# pc_healthypi_move_nRF5340_v5.net
KiCad netlist of a schematic drawn in EAGLE
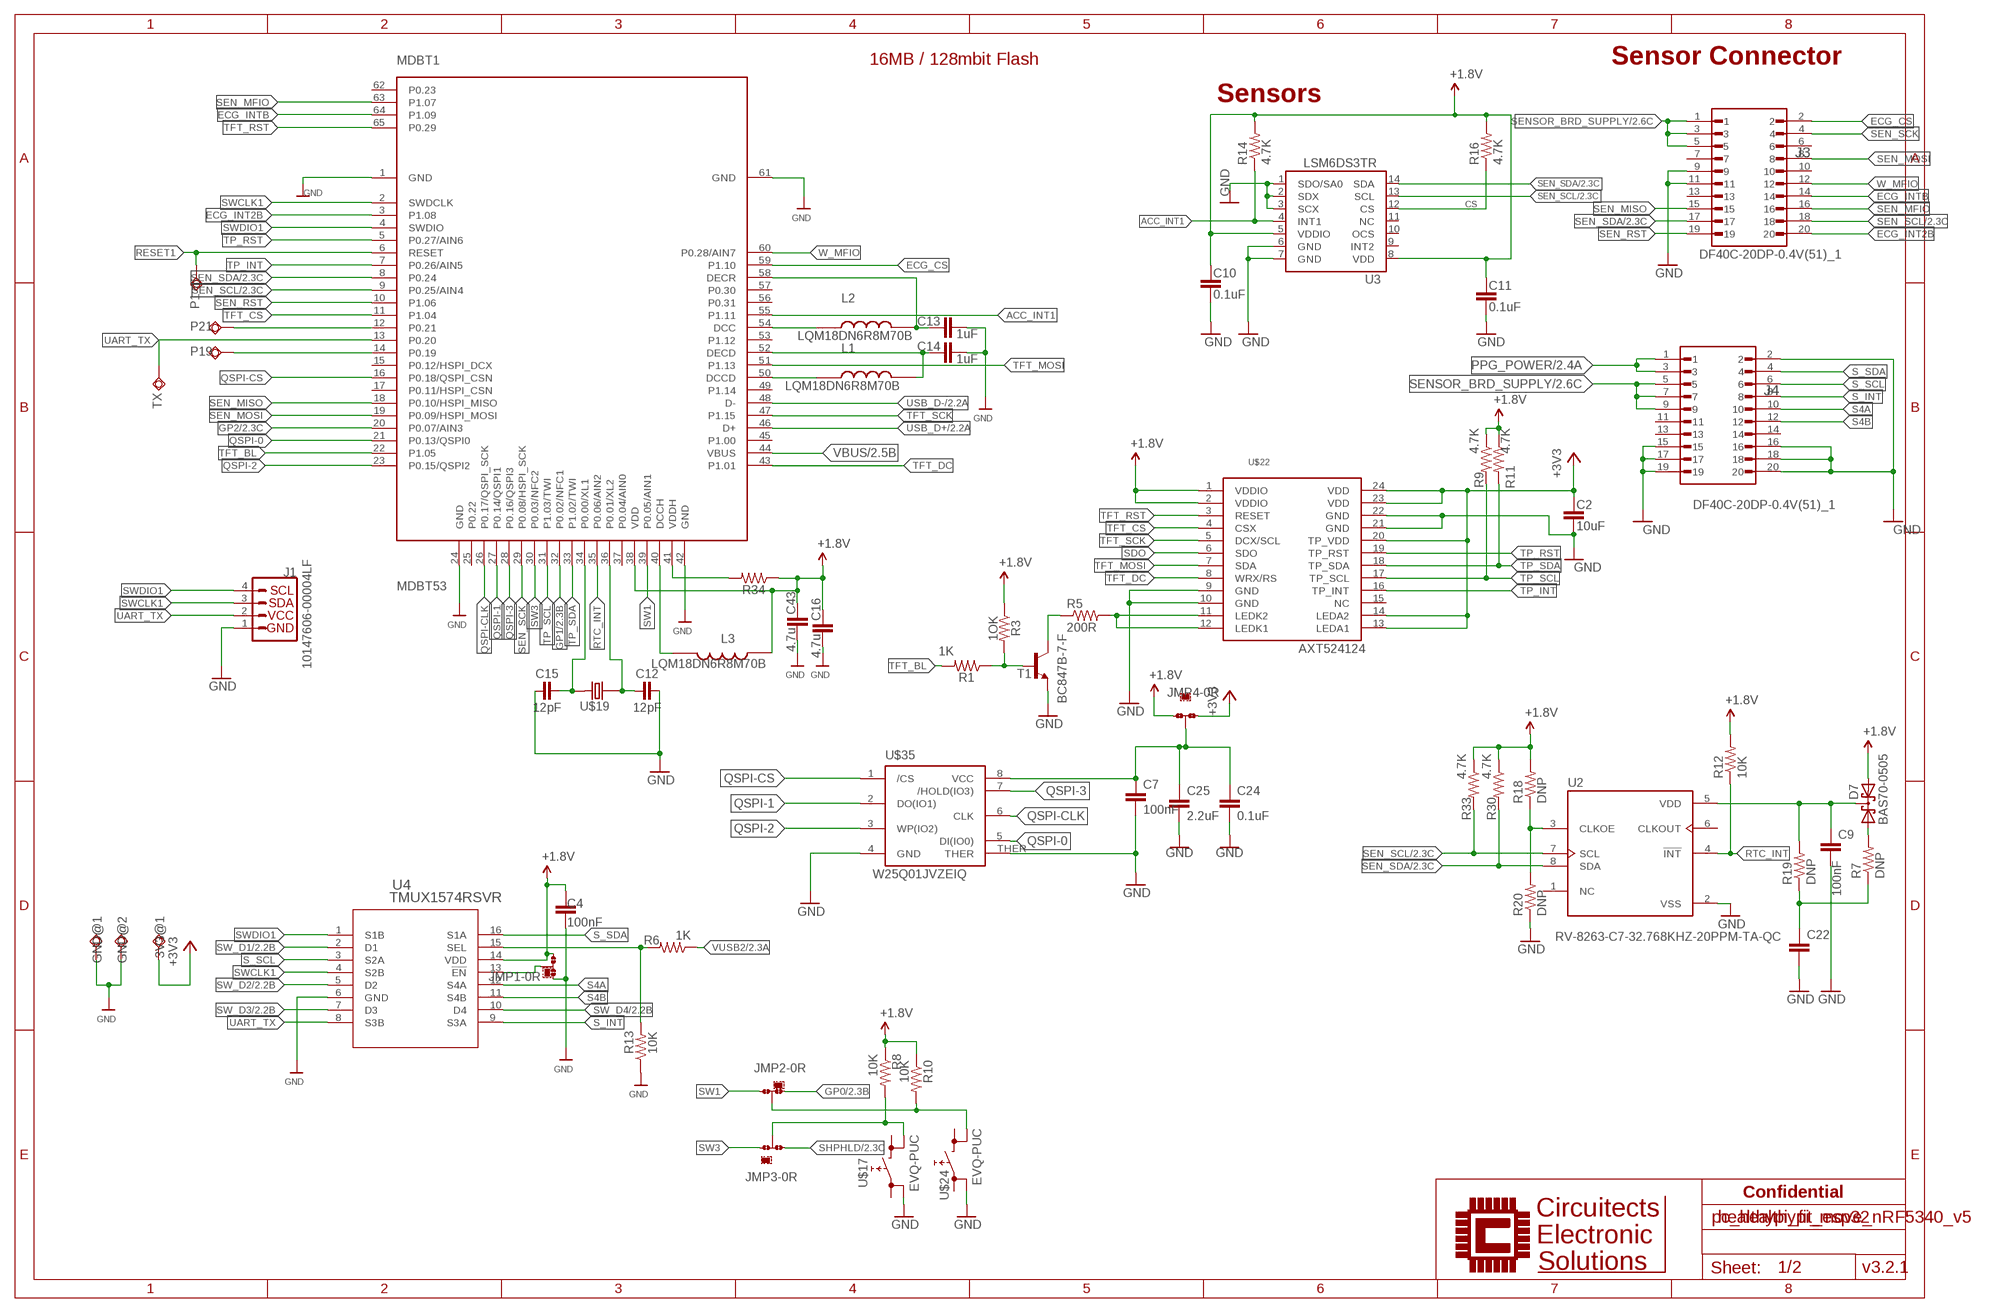
[diagram p0: schematic, sheet 1]
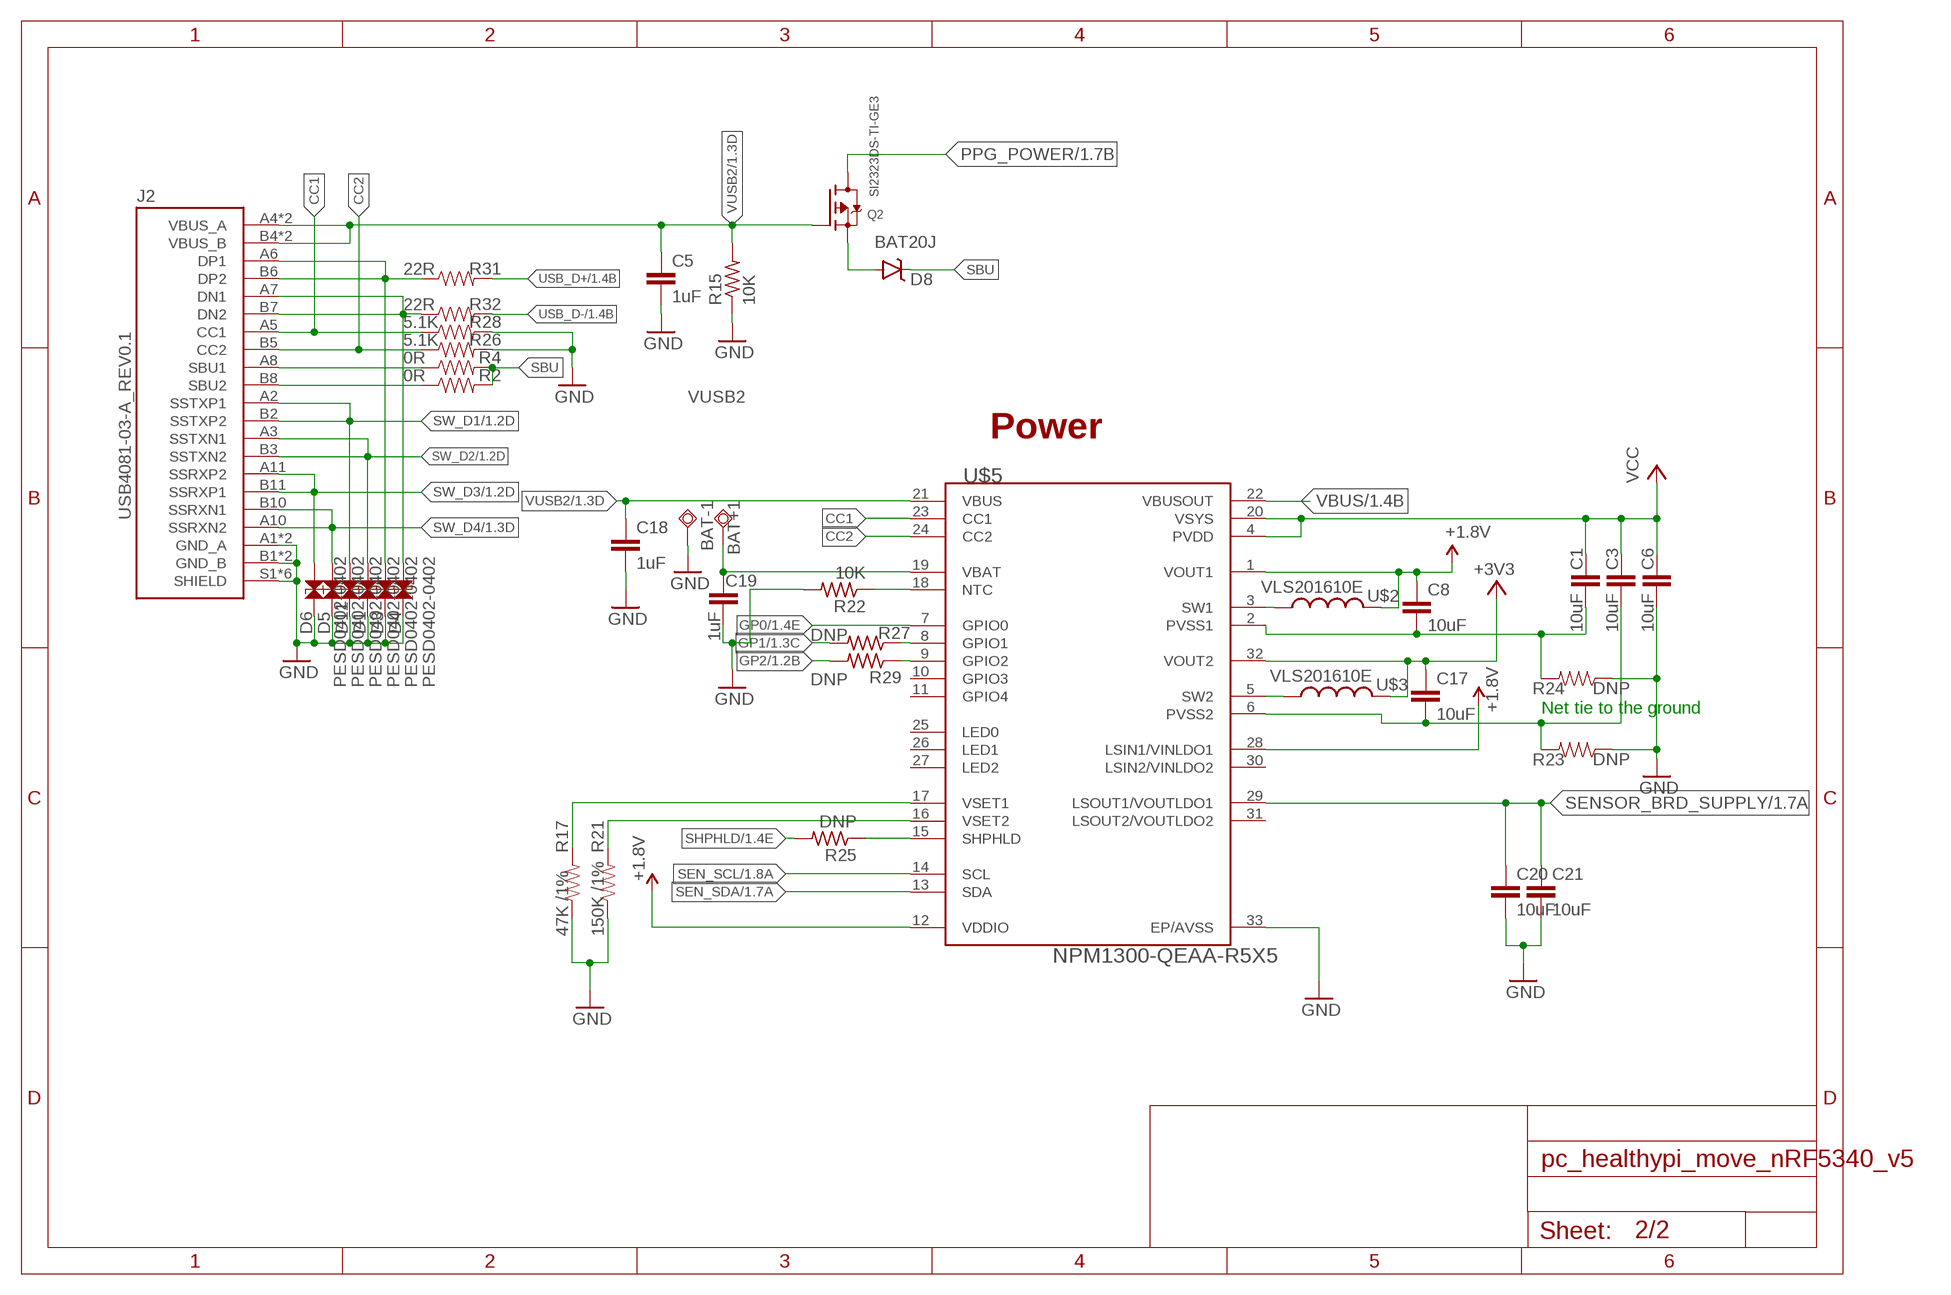
[diagram p1: schematic, sheet 2]

(export (version "E")
  (design (tool "Eeschema 10.0.6"))
  (components
    (comp (ref "3V3@1")
      (value "TPSQTP13SQ")
      (footprint "eagle-import:TP13SQ")
      (libsource (lib "eagle-import") (part "TPSQTP13SQ"))
    )
    (comp (ref "C2")
      (value "10uF")
      (footprint "eagle-import:0603@1")
      (libsource (lib "eagle-import") (part "0.1UF-0603-100V-10%"))
    )
    (comp (ref "C4")
      (value "100nF")
      (footprint "eagle-import:0402-TIGHT")
      (libsource (lib "eagle-import") (part "2.2UF-0402_TIGHT-10V-10%-X5R"))
    )
    (comp (ref "C7")
      (value "100nF")
      (footprint "eagle-import:C0402")
      (libsource (lib "eagle-import") (part "C-EUC0402"))
    )
    (comp (ref "C9")
      (value "100nF")
      (footprint "eagle-import:C0402")
      (libsource (lib "eagle-import") (part "C-EUC0402"))
    )
    (comp (ref "C10")
      (value "0.1uF")
      (footprint "eagle-import:0402-TIGHT")
      (libsource (lib "eagle-import") (part "0.1UF-0402T-6.3V-10%-X7R"))
    )
    (comp (ref "C11")
      (value "0.1uF")
      (footprint "eagle-import:0402-TIGHT")
      (libsource (lib "eagle-import") (part "0.1UF-0402T-6.3V-10%-X7R"))
    )
    (comp (ref "C12")
      (value "12pF")
      (footprint "eagle-import:C0402")
      (libsource (lib "eagle-import") (part "CAPACITORS-0402"))
    )
    (comp (ref "C13")
      (value "1uF")
      (footprint "eagle-import:0402-TIGHT")
      (libsource (lib "eagle-import") (part "2.2UF-0402_TIGHT-10V-10%-X5R"))
    )
    (comp (ref "C14")
      (value "1uF")
      (footprint "eagle-import:0402-TIGHT")
      (libsource (lib "eagle-import") (part "2.2UF-0402_TIGHT-10V-10%-X5R"))
    )
    (comp (ref "C15")
      (value "12pF")
      (footprint "eagle-import:C0402")
      (libsource (lib "eagle-import") (part "CAPACITORS-0402"))
    )
    (comp (ref "C16")
      (value "4.7u")
      (footprint "eagle-import:C0402")
      (libsource (lib "eagle-import") (part "C-EUC0402"))
    )
    (comp (ref "C22")
      (value "C-EUC1210")
      (footprint "eagle-import:C1210")
      (libsource (lib "eagle-import") (part "C-EUC1210"))
    )
    (comp (ref "C24")
      (value "0.1uF")
      (footprint "eagle-import:0402-TIGHT")
      (libsource (lib "eagle-import") (part "0.1UF-0402T-6.3V-10%-X7R"))
    )
    (comp (ref "C25")
      (value "2.2uF")
      (footprint "eagle-import:0402-TIGHT")
      (libsource (lib "eagle-import") (part "2.2UF-0402_TIGHT-10V-10%-X5R"))
    )
    (comp (ref "C43")
      (value "4.7u")
      (footprint "eagle-import:C0402")
      (libsource (lib "eagle-import") (part "C-EUC0402"))
    )
    (comp (ref "D7")
      (value "BAS70-0505")
      (footprint "eagle-import:SOT23")
      (fields (field (name "MF") "Diotec") (field (name "MP") "BAS70-05"))
      (libsource (lib "eagle-import") (part "BAS70-0505"))
    )
    (comp (ref "GND@1")
      (value "TPSQTP13SQ")
      (footprint "eagle-import:TP13SQ")
      (libsource (lib "eagle-import") (part "TPSQTP13SQ"))
    )
    (comp (ref "GND@2")
      (value "TPSQTP13SQ")
      (footprint "eagle-import:TP13SQ")
      (libsource (lib "eagle-import") (part "TPSQTP13SQ"))
    )
    (comp (ref "J1")
      (value "10147606-00004LF")
      (footprint "eagle-import:JST04_1MM_RA")
      (libsource (lib "eagle-import") (part "QWIIC_CONNECTORJS-1MM"))
    )
    (comp (ref "J3")
      (value "DF40C-20DP-0.4V(51)_1")
      (footprint "eagle-import:HRS_DF40C-20DP-0.4V(51)")
      (fields (field (name "MANUFACTURER") "Hirose Electric"))
      (libsource (lib "eagle-import") (part "DF40C-20DP-0.4V(51)_1"))
    )
    (comp (ref "J4")
      (value "DF40C-20DP-0.4V(51)_1")
      (footprint "eagle-import:HRS_DF40C-20DP-0.4V(51)")
      (fields (field (name "MANUFACTURER") "Hirose Electric"))
      (libsource (lib "eagle-import") (part "DF40C-20DP-0.4V(51)_1"))
    )
    (comp (ref "JMP1")
      (value "0R-JUMPB")
      (footprint "eagle-import:B0R-JMP")
      (libsource (lib "eagle-import") (part "0R-JUMPB"))
    )
    (comp (ref "JMP2")
      (value "0R-JUMPB")
      (footprint "eagle-import:B0R-JMP")
      (libsource (lib "eagle-import") (part "0R-JUMPB"))
    )
    (comp (ref "JMP3")
      (value "0R-JUMPB")
      (footprint "eagle-import:B0R-JMP")
      (libsource (lib "eagle-import") (part "0R-JUMPB"))
    )
    (comp (ref "JMP4")
      (value "0R-JUMPB")
      (footprint "eagle-import:B0R-JMP")
      (libsource (lib "eagle-import") (part "0R-JUMPB"))
    )
    (comp (ref "L1")
      (value "LQM18DN6R8M70B")
      (footprint "eagle-import:INDC1608X95N")
      (fields (field (name "MF") "Murata"))
      (libsource (lib "eagle-import") (part "LQM18DN6R8M70B"))
    )
    (comp (ref "L2")
      (value "LQM18DN6R8M70B")
      (footprint "eagle-import:INDC1608X95N")
      (fields (field (name "MF") "Murata"))
      (libsource (lib "eagle-import") (part "LQM18DN6R8M70B"))
    )
    (comp (ref "L3")
      (value "LQM18DN6R8M70B")
      (footprint "eagle-import:INDC1608X95N")
      (fields (field (name "MF") "Murata"))
      (libsource (lib "eagle-import") (part "LQM18DN6R8M70B"))
    )
    (comp (ref "MDBT1")
      (value "MDBT53")
      (footprint "eagle-import:MDBT53")
      (libsource (lib "eagle-import") (part "MDBT53"))
    )
    (comp (ref "P1")
      (value "TPSQTP13SQ")
      (footprint "eagle-import:TP13SQ")
      (libsource (lib "eagle-import") (part "TPSQTP13SQ"))
    )
    (comp (ref "P19")
      (value "TPSQTP13SQ")
      (footprint "eagle-import:TP13SQ")
      (libsource (lib "eagle-import") (part "TPSQTP13SQ"))
    )
    (comp (ref "P21")
      (value "TPSQTP13SQ")
      (footprint "eagle-import:TP13SQ")
      (libsource (lib "eagle-import") (part "TPSQTP13SQ"))
    )
    (comp (ref "R1")
      (value "200")
      (footprint "eagle-import:R0402")
      (libsource (lib "eagle-import") (part "R-US_R0402"))
    )
    (comp (ref "R3")
      (value "200")
      (footprint "eagle-import:R0402")
      (libsource (lib "eagle-import") (part "R-US_R0402"))
    )
    (comp (ref "R5")
      (value "200R")
      (footprint "eagle-import:R0402")
      (libsource (lib "eagle-import") (part "R-US_R0402"))
    )
    (comp (ref "R6")
      (value "1K")
      (footprint "eagle-import:0402-RES")
      (libsource (lib "eagle-import") (part "RESISTOR0402-RES"))
    )
    (comp (ref "R7")
      (value "DNP")
      (footprint "eagle-import:R0402")
      (libsource (lib "eagle-import") (part "R-US_R0402"))
    )
    (comp (ref "R8")
      (value "10K")
      (footprint "eagle-import:R0402")
      (libsource (lib "eagle-import") (part "R-US_R0402"))
    )
    (comp (ref "R9")
      (value "4.7K")
      (footprint "eagle-import:R0402")
      (libsource (lib "eagle-import") (part "R-US_R0402"))
    )
    (comp (ref "R10")
      (value "10K")
      (footprint "eagle-import:R0402")
      (libsource (lib "eagle-import") (part "R-US_R0402"))
    )
    (comp (ref "R11")
      (value "4.7K")
      (footprint "eagle-import:R0402")
      (libsource (lib "eagle-import") (part "R-US_R0402"))
    )
    (comp (ref "R12")
      (value "10K")
      (footprint "eagle-import:R0402")
      (libsource (lib "eagle-import") (part "R-US_R0402"))
    )
    (comp (ref "R13")
      (value "10K")
      (footprint "eagle-import:R0402")
      (libsource (lib "eagle-import") (part "R-US_R0402"))
    )
    (comp (ref "R14")
      (value "4.7K")
      (footprint "eagle-import:R0402")
      (libsource (lib "eagle-import") (part "R-US_R0402"))
    )
    (comp (ref "R16")
      (value "4.7K")
      (footprint "eagle-import:R0402")
      (libsource (lib "eagle-import") (part "R-US_R0402"))
    )
    (comp (ref "R18")
      (value "DNP")
      (footprint "eagle-import:R0402")
      (libsource (lib "eagle-import") (part "R-US_R0402"))
    )
    (comp (ref "R19")
      (value "DNP")
      (footprint "eagle-import:R0402")
      (libsource (lib "eagle-import") (part "R-US_R0402"))
    )
    (comp (ref "R20")
      (value "DNP")
      (footprint "eagle-import:R0402")
      (libsource (lib "eagle-import") (part "R-US_R0402"))
    )
    (comp (ref "R30")
      (value "4.7K")
      (footprint "eagle-import:R0402")
      (libsource (lib "eagle-import") (part "R-US_R0402"))
    )
    (comp (ref "R33")
      (value "4.7K")
      (footprint "eagle-import:R0402")
      (libsource (lib "eagle-import") (part "R-US_R0402"))
    )
    (comp (ref "R34")
      (value "200")
      (footprint "eagle-import:R0402")
      (libsource (lib "eagle-import") (part "R-US_R0402"))
    )
    (comp (ref "T1")
      (value "BC847B-7-F")
      (footprint "eagle-import:SOT23-BEC")
      (libsource (lib "eagle-import") (part "-NPN-SOT23-BECMMBT2222ALT1"))
    )
    (comp (ref "TX")
      (value "TPSQTP13SQ")
      (footprint "eagle-import:TP13SQ")
      (libsource (lib "eagle-import") (part "TPSQTP13SQ"))
    )
    (comp (ref "U$17")
      (value "EVQ-PUC")
      (footprint "eagle-import:EVQ-PUC")
      (libsource (lib "eagle-import") (part "EVQ-PUC"))
    )
    (comp (ref "U$19")
      (value "520-327-12.5-34B(32.768KHZ)")
      (footprint "eagle-import:ECX-31B")
      (libsource (lib "eagle-import") (part "ECS-X-34B"))
    )
    (comp (ref "U$22")
      (value "AXT524124")
      (footprint "eagle-import:AXT524124")
      (libsource (lib "eagle-import") (part "AXT524124"))
    )
    (comp (ref "U$24")
      (value "EVQ-PUC")
      (footprint "eagle-import:EVQ-PUC")
      (libsource (lib "eagle-import") (part "EVQ-PUC"))
    )
    (comp (ref "U$35")
      (value "W25Q01JVZEIQ")
      (footprint "eagle-import:WSON-08")
      (libsource (lib "eagle-import") (part "W25N01GVZEIG"))
    )
    (comp (ref "U2")
      (value "RV-8263-C7-32.768KHZ-20PPM-TA-QC")
      (footprint "eagle-import:IC_RV-8263-C7-32.768KHZ-20PPM-TA-QC")
      (fields (field (name "MF") "Micro Crystal"))
      (libsource (lib "eagle-import") (part "RV-8263-C7-32.768KHZ-20PPM-TA-QC"))
    )
    (comp (ref "U3")
      (value "LSM6DS3TR")
      (footprint "eagle-import:LGA14L")
      (libsource (lib "eagle-import") (part "LSM6DS3"))
    )
    (comp (ref "U4")
      (value "TMUX1574RSVR")
      (footprint "eagle-import:RSV16_TEX")
      (fields (field (name "COPYRIGHT") "Copyright (C) 2024 Ultra Librarian. All rights reserved."))
      (libsource (lib "eagle-import") (part "TMUX1574RSVR"))
    )
    (comp (ref "BAT+1")
      (value "TPSQTP13SQ")
      (footprint "eagle-import:TP13SQ")
      (libsource (lib "eagle-import") (part "TPSQTP13SQ"))
    )
    (comp (ref "BAT-1")
      (value "TPSQTP13SQ")
      (footprint "eagle-import:TP13SQ")
      (libsource (lib "eagle-import") (part "TPSQTP13SQ"))
    )
    (comp (ref "C1")
      (value "10uF")
      (footprint "eagle-import:0402-TIGHT")
      (libsource (lib "eagle-import") (part "2.2UF-0402_TIGHT-10V-10%-X5R"))
    )
    (comp (ref "C3")
      (value "10uF")
      (footprint "eagle-import:0402-TIGHT")
      (libsource (lib "eagle-import") (part "2.2UF-0402_TIGHT-10V-10%-X5R"))
    )
    (comp (ref "C5")
      (value "1uF")
      (footprint "eagle-import:0402-TIGHT")
      (libsource (lib "eagle-import") (part "2.2UF-0402_TIGHT-10V-10%-X5R"))
    )
    (comp (ref "C6")
      (value "10uF")
      (footprint "eagle-import:0402-TIGHT")
      (libsource (lib "eagle-import") (part "2.2UF-0402_TIGHT-10V-10%-X5R"))
    )
    (comp (ref "C8")
      (value "10uF")
      (footprint "eagle-import:0402-TIGHT")
      (libsource (lib "eagle-import") (part "2.2UF-0402_TIGHT-10V-10%-X5R"))
    )
    (comp (ref "C17")
      (value "10uF")
      (footprint "eagle-import:0402-TIGHT")
      (libsource (lib "eagle-import") (part "2.2UF-0402_TIGHT-10V-10%-X5R"))
    )
    (comp (ref "C18")
      (value "1uF")
      (footprint "eagle-import:0402-TIGHT")
      (libsource (lib "eagle-import") (part "2.2UF-0402_TIGHT-10V-10%-X5R"))
    )
    (comp (ref "C19")
      (value "1uF")
      (footprint "eagle-import:0402-TIGHT")
      (libsource (lib "eagle-import") (part "2.2UF-0402_TIGHT-10V-10%-X5R"))
    )
    (comp (ref "C20")
      (value "10uF")
      (footprint "eagle-import:0402-TIGHT")
      (libsource (lib "eagle-import") (part "2.2UF-0402_TIGHT-10V-10%-X5R"))
    )
    (comp (ref "C21")
      (value "10uF")
      (footprint "eagle-import:0402-TIGHT")
      (libsource (lib "eagle-import") (part "2.2UF-0402_TIGHT-10V-10%-X5R"))
    )
    (comp (ref "D1")
      (value "PESD0402-0402")
      (footprint "eagle-import:0402")
      (fields
        (field (name "DIGIKEY_PART") "PESD0402-140CT-ND")
        (field (name "MOUSE_PART") "650-PESD0402-140")
      )
      (libsource (lib "eagle-import") (part "PESD0402-0402"))
    )
    (comp (ref "D3")
      (value "PESD0402-0402")
      (footprint "eagle-import:0402")
      (fields
        (field (name "DIGIKEY_PART") "PESD0402-140CT-ND")
        (field (name "MOUSE_PART") "650-PESD0402-140")
      )
      (libsource (lib "eagle-import") (part "PESD0402-0402"))
    )
    (comp (ref "D4")
      (value "PESD0402-0402")
      (footprint "eagle-import:0402")
      (fields
        (field (name "DIGIKEY_PART") "PESD0402-140CT-ND")
        (field (name "MOUSE_PART") "650-PESD0402-140")
      )
      (libsource (lib "eagle-import") (part "PESD0402-0402"))
    )
    (comp (ref "D5")
      (value "PESD0402-0402")
      (footprint "eagle-import:0402")
      (fields
        (field (name "DIGIKEY_PART") "PESD0402-140CT-ND")
        (field (name "MOUSE_PART") "650-PESD0402-140")
      )
      (libsource (lib "eagle-import") (part "PESD0402-0402"))
    )
    (comp (ref "D6")
      (value "PESD0402-0402")
      (footprint "eagle-import:0402")
      (fields
        (field (name "DIGIKEY_PART") "PESD0402-140CT-ND")
        (field (name "MOUSE_PART") "650-PESD0402-140")
      )
      (libsource (lib "eagle-import") (part "PESD0402-0402"))
    )
    (comp (ref "D8")
      (value "BAT20J")
      (footprint "eagle-import:SOD-323")
      (libsource (lib "eagle-import") (part "DIODE-SCHOTTKY-BAT20J"))
    )
    (comp (ref "D11")
      (value "PESD0402-0402")
      (footprint "eagle-import:0402")
      (fields
        (field (name "DIGIKEY_PART") "PESD0402-140CT-ND")
        (field (name "MOUSE_PART") "650-PESD0402-140")
      )
      (libsource (lib "eagle-import") (part "PESD0402-0402"))
    )
    (comp (ref "J2")
      (value "USB4081-03-A_REV0.1")
      (footprint "eagle-import:GCT_USB4081-03-A_REV0.1")
      (fields (field (name "MF") "Global Connector Technology") (field (name "MP") "USB4081-03-A"))
      (libsource (lib "eagle-import") (part "USB4081-03-A_REV0.1"))
    )
    (comp (ref "Q2")
      (value "SI2323DS-TI-GE3")
      (footprint "eagle-import:SOT23-R")
      (libsource (lib "eagle-import") (part "MOSFET-P"))
    )
    (comp (ref "R2")
      (value "0R")
      (footprint "eagle-import:0402-RES")
      (libsource (lib "eagle-import") (part "RESISTOR0402-RES"))
    )
    (comp (ref "R4")
      (value "0R")
      (footprint "eagle-import:0402-RES")
      (libsource (lib "eagle-import") (part "RESISTOR0402-RES"))
    )
    (comp (ref "R15")
      (value "10K")
      (footprint "eagle-import:R0402")
      (libsource (lib "eagle-import") (part "R-US_R0402"))
    )
    (comp (ref "R17")
      (value "47K /1%")
      (footprint "eagle-import:0402-RES")
      (libsource (lib "eagle-import") (part "RESISTOR0402-RES"))
    )
    (comp (ref "R21")
      (value "150K /1%")
      (footprint "eagle-import:0402-RES")
      (libsource (lib "eagle-import") (part "RESISTOR0402-RES"))
    )
    (comp (ref "R22")
      (value "10K")
      (footprint "eagle-import:R0402")
      (libsource (lib "eagle-import") (part "R-US_R0402"))
    )
    (comp (ref "R23")
      (value "DNP")
      (footprint "eagle-import:0402-RES")
      (libsource (lib "eagle-import") (part "RESISTOR0402-RES"))
    )
    (comp (ref "R24")
      (value "DNP")
      (footprint "eagle-import:0402-RES")
      (libsource (lib "eagle-import") (part "RESISTOR0402-RES"))
    )
    (comp (ref "R25")
      (value "DNP")
      (footprint "eagle-import:R0402")
      (libsource (lib "eagle-import") (part "R-US_R0402"))
    )
    (comp (ref "R26")
      (value "5.1K")
      (footprint "eagle-import:0402-RES")
      (libsource (lib "eagle-import") (part "RESISTOR0402-RES"))
    )
    (comp (ref "R27")
      (value "DNP")
      (footprint "eagle-import:R0402")
      (libsource (lib "eagle-import") (part "R-US_R0402"))
    )
    (comp (ref "R28")
      (value "5.1K")
      (footprint "eagle-import:0402-RES")
      (libsource (lib "eagle-import") (part "RESISTOR0402-RES"))
    )
    (comp (ref "R29")
      (value "DNP")
      (footprint "eagle-import:R0402")
      (libsource (lib "eagle-import") (part "R-US_R0402"))
    )
    (comp (ref "R31")
      (value "22R")
      (footprint "eagle-import:0402-RES")
      (libsource (lib "eagle-import") (part "RESISTOR0402-RES"))
    )
    (comp (ref "R32")
      (value "22R")
      (footprint "eagle-import:0402-RES")
      (libsource (lib "eagle-import") (part "RESISTOR0402-RES"))
    )
    (comp (ref "U$2")
      (value "VLS201610E")
      (footprint "eagle-import:VLS201610E")
      (libsource (lib "eagle-import") (part "VLS201610E"))
    )
    (comp (ref "U$3")
      (value "VLS201610E")
      (footprint "eagle-import:VLS201610E")
      (libsource (lib "eagle-import") (part "VLS201610E"))
    )
    (comp (ref "U$5")
      (value "NPM1300-QEAA-R5X5")
      (footprint "eagle-import:QFN32_5X5MC_MCH")
      (libsource (lib "eagle-import") (part "NPM1300-QEAA-R5X5"))
    )
  )
  (nets
    (net (code "1") (name "+1.8V") (class "Default")
      (node (ref "C10") (pin "1") (pinfunction "1_1") (pintype "passive"))
      (node (ref "C11") (pin "1") (pinfunction "1_1") (pintype "passive"))
      (node (ref "C16") (pin "1") (pinfunction "1_1") (pintype "passive"))
      (node (ref "C4") (pin "1") (pinfunction "1_1") (pintype "passive"))
      (node (ref "C43") (pin "1") (pinfunction "1_1") (pintype "passive"))
      (node (ref "C8") (pin "1") (pinfunction "1_1") (pintype "passive"))
      (node (ref "D7") (pin "2") (pinfunction "A2_2") (pintype "passive"))
      (node (ref "JMP1") (pin "3") (pinfunction "3_3") (pintype "passive"))
      (node (ref "JMP4") (pin "3") (pinfunction "3_3") (pintype "passive"))
      (node (ref "L3") (pin "1") (pinfunction "1_1") (pintype "passive"))
      (node (ref "MDBT1") (pin "38") (pinfunction "VDD_38") (pintype "bidirectional"))
      (node (ref "R10") (pin "1") (pinfunction "1_1") (pintype "passive"))
      (node (ref "R11") (pin "1") (pinfunction "1_1") (pintype "passive"))
      (node (ref "R12") (pin "2") (pinfunction "2_2") (pintype "passive"))
      (node (ref "R14") (pin "2") (pinfunction "2_2") (pintype "passive"))
      (node (ref "R16") (pin "2") (pinfunction "2_2") (pintype "passive"))
      (node (ref "R18") (pin "2") (pinfunction "2_2") (pintype "passive"))
      (node (ref "R3") (pin "1") (pinfunction "1_1") (pintype "passive"))
      (node (ref "R30") (pin "1") (pinfunction "1_1") (pintype "passive"))
      (node (ref "R33") (pin "1") (pinfunction "1_1") (pintype "passive"))
      (node (ref "R34") (pin "1") (pinfunction "1_1") (pintype "passive"))
      (node (ref "R8") (pin "1") (pinfunction "1_1") (pintype "passive"))
      (node (ref "R9") (pin "1") (pinfunction "1_1") (pintype "passive"))
      (node (ref "U$2") (pin "2") (pinfunction "2_2") (pintype "passive"))
      (node (ref "U$22") (pin "1") (pinfunction "VDDIO_1") (pintype "bidirectional"))
      (node (ref "U$22") (pin "2") (pinfunction "VDDIO_2") (pintype "bidirectional"))
      (node (ref "U$5") (pin "1") (pinfunction "VOUT1_1") (pintype "bidirectional"))
      (node (ref "U$5") (pin "12") (pinfunction "VDDIO_12") (pintype "bidirectional"))
      (node (ref "U$5") (pin "28") (pinfunction "LSIN1/VINLDO1_28") (pintype "bidirectional"))
      (node (ref "U3") (pin "5") (pinfunction "VDDIO_5") (pintype "bidirectional"))
      (node (ref "U3") (pin "8") (pinfunction "VDD_8") (pintype "bidirectional"))
      (node (ref "U4") (pin "14") (pinfunction "VDD_14") (pintype "power_in"))
    )
    (net (code "2") (name "+3V3") (class "Default")
      (node (ref "3V3@1") (pin "TP") (pinfunction "TP_TP") (pintype "input"))
      (node (ref "C17") (pin "1") (pinfunction "1_1") (pintype "passive"))
      (node (ref "C2") (pin "1") (pinfunction "1_1") (pintype "passive"))
      (node (ref "JMP4") (pin "1") (pinfunction "1_1") (pintype "passive"))
      (node (ref "U$22") (pin "13") (pinfunction "LEDA1_13") (pintype "bidirectional"))
      (node (ref "U$22") (pin "14") (pinfunction "LEDA2_14") (pintype "bidirectional"))
      (node (ref "U$22") (pin "20") (pinfunction "TP_VDD_20") (pintype "bidirectional"))
      (node (ref "U$22") (pin "23") (pinfunction "VDD_23") (pintype "bidirectional"))
      (node (ref "U$22") (pin "24") (pinfunction "VDD_24") (pintype "bidirectional"))
      (node (ref "U$3") (pin "2") (pinfunction "2_2") (pintype "passive"))
      (node (ref "U$5") (pin "32") (pinfunction "VOUT2_32") (pintype "bidirectional"))
    )
    (net (code "3") (name "ACC_INT1") (class "Default")
      (node (ref "MDBT1") (pin "55") (pinfunction "P1.11_55") (pintype "bidirectional"))
      (node (ref "R14") (pin "1") (pinfunction "1_1") (pintype "passive"))
      (node (ref "U3") (pin "4") (pinfunction "INT1_4") (pintype "bidirectional"))
    )
    (net (code "4") (name "CC1") (class "Default")
      (node (ref "J2") (pin "A5") (pinfunction "CC1_A5") (pintype "bidirectional"))
      (node (ref "R28") (pin "1") (pinfunction "1_1") (pintype "passive"))
      (node (ref "U$5") (pin "23") (pinfunction "CC1_23") (pintype "bidirectional"))
    )
    (net (code "5") (name "CC2") (class "Default")
      (node (ref "J2") (pin "B5") (pinfunction "CC2_B5") (pintype "bidirectional"))
      (node (ref "R26") (pin "1") (pinfunction "1_1") (pintype "passive"))
      (node (ref "U$5") (pin "24") (pinfunction "CC2_24") (pintype "bidirectional"))
    )
    (net (code "6") (name "CS") (class "Default")
      (node (ref "R16") (pin "1") (pinfunction "1_1") (pintype "passive"))
      (node (ref "U3") (pin "12") (pinfunction "CS_12") (pintype "bidirectional"))
    )
    (net (code "7") (name "ECG_CS") (class "Default")
      (node (ref "J3") (pin "2") (pinfunction "2_2") (pintype "passive"))
      (node (ref "MDBT1") (pin "59") (pinfunction "P1.10_59") (pintype "bidirectional"))
    )
    (net (code "8") (name "ECG_INT2B") (class "Default")
      (node (ref "J3") (pin "20") (pinfunction "20_20") (pintype "passive"))
      (node (ref "MDBT1") (pin "3") (pinfunction "P1.08_3") (pintype "bidirectional"))
    )
    (net (code "9") (name "ECG_INTB") (class "Default")
      (node (ref "J3") (pin "14") (pinfunction "14_14") (pintype "passive"))
      (node (ref "MDBT1") (pin "64") (pinfunction "P1.09_64") (pintype "bidirectional"))
    )
    (net (code "10") (name "GND") (class "Default")
      (node (ref "BAT-1") (pin "TP") (pinfunction "TP_TP") (pintype "input"))
      (node (ref "C10") (pin "2") (pinfunction "2_2") (pintype "passive"))
      (node (ref "C11") (pin "2") (pinfunction "2_2") (pintype "passive"))
      (node (ref "C12") (pin "2") (pinfunction "2_2") (pintype "passive"))
      (node (ref "C13") (pin "2") (pinfunction "2_2") (pintype "passive"))
      (node (ref "C14") (pin "2") (pinfunction "2_2") (pintype "passive"))
      (node (ref "C15") (pin "1") (pinfunction "1_1") (pintype "passive"))
      (node (ref "C16") (pin "2") (pinfunction "2_2") (pintype "passive"))
      (node (ref "C18") (pin "2") (pinfunction "2_2") (pintype "passive"))
      (node (ref "C19") (pin "2") (pinfunction "2_2") (pintype "passive"))
      (node (ref "C2") (pin "2") (pinfunction "2_2") (pintype "passive"))
      (node (ref "C20") (pin "2") (pinfunction "2_2") (pintype "passive"))
      (node (ref "C21") (pin "2") (pinfunction "2_2") (pintype "passive"))
      (node (ref "C22") (pin "2") (pinfunction "2_2") (pintype "passive"))
      (node (ref "C24") (pin "2") (pinfunction "2_2") (pintype "passive"))
      (node (ref "C25") (pin "2") (pinfunction "2_2") (pintype "passive"))
      (node (ref "C4") (pin "2") (pinfunction "2_2") (pintype "passive"))
      (node (ref "C43") (pin "2") (pinfunction "2_2") (pintype "passive"))
      (node (ref "C5") (pin "2") (pinfunction "2_2") (pintype "passive"))
      (node (ref "C6") (pin "2") (pinfunction "2_2") (pintype "passive"))
      (node (ref "C7") (pin "2") (pinfunction "2_2") (pintype "passive"))
      (node (ref "C9") (pin "2") (pinfunction "2_2") (pintype "passive"))
      (node (ref "D1") (pin "1") (pinfunction "1_1") (pintype "bidirectional"))
      (node (ref "D11") (pin "1") (pinfunction "1_1") (pintype "bidirectional"))
      (node (ref "D3") (pin "1") (pinfunction "1_1") (pintype "bidirectional"))
      (node (ref "D4") (pin "1") (pinfunction "1_1") (pintype "bidirectional"))
      (node (ref "D5") (pin "1") (pinfunction "1_1") (pintype "bidirectional"))
      (node (ref "D6") (pin "1") (pinfunction "1_1") (pintype "bidirectional"))
      (node (ref "GND@1") (pin "TP") (pinfunction "TP_TP") (pintype "input"))
      (node (ref "GND@2") (pin "TP") (pinfunction "TP_TP") (pintype "input"))
      (node (ref "J1") (pin "1") (pinfunction "1_1") (pintype "power_in"))
      (node (ref "J2") (pin "A1") (pinfunction "GND_A_A1") (pintype "power_in"))
      (node (ref "J2") (pin "A12") (pinfunction "GND_A_A12") (pintype "power_in"))
      (node (ref "J2") (pin "B1") (pinfunction "GND_B_B1") (pintype "power_in"))
      (node (ref "J2") (pin "B12") (pinfunction "GND_B_B12") (pintype "power_in"))
      (node (ref "J2") (pin "S1") (pinfunction "SHIELD_S1") (pintype "passive"))
      (node (ref "J2") (pin "S2") (pinfunction "SHIELD_S2") (pintype "passive"))
      (node (ref "J2") (pin "S3") (pinfunction "SHIELD_S3") (pintype "passive"))
      (node (ref "J2") (pin "S4") (pinfunction "SHIELD_S4") (pintype "passive"))
      (node (ref "J2") (pin "S5") (pinfunction "SHIELD_S5") (pintype "passive"))
      (node (ref "J2") (pin "S6") (pinfunction "SHIELD_S6") (pintype "passive"))
      (node (ref "J3") (pin "11") (pinfunction "11_11") (pintype "passive"))
      (node (ref "J3") (pin "9") (pinfunction "9_9") (pintype "passive"))
      (node (ref "J4") (pin "15") (pinfunction "15_15") (pintype "passive"))
      (node (ref "J4") (pin "16") (pinfunction "16_16") (pintype "passive"))
      (node (ref "J4") (pin "17") (pinfunction "17_17") (pintype "passive"))
      (node (ref "J4") (pin "18") (pinfunction "18_18") (pintype "passive"))
      (node (ref "J4") (pin "19") (pinfunction "19_19") (pintype "passive"))
      (node (ref "J4") (pin "2") (pinfunction "2_2") (pintype "passive"))
      (node (ref "J4") (pin "20") (pinfunction "20_20") (pintype "passive"))
      (node (ref "JMP1") (pin "1") (pinfunction "1_1") (pintype "passive"))
      (node (ref "MDBT1") (pin "1") (pinfunction "GND_1") (pintype "bidirectional"))
      (node (ref "MDBT1") (pin "24") (pinfunction "GND_24") (pintype "bidirectional"))
      (node (ref "MDBT1") (pin "42") (pinfunction "GND_42") (pintype "bidirectional"))
      (node (ref "MDBT1") (pin "61") (pinfunction "GND_61") (pintype "bidirectional"))
      (node (ref "R13") (pin "1") (pinfunction "1_1") (pintype "passive"))
      (node (ref "R15") (pin "1") (pinfunction "1_1") (pintype "passive"))
      (node (ref "R17") (pin "1") (pinfunction "1_1") (pintype "passive"))
      (node (ref "R20") (pin "1") (pinfunction "1_1") (pintype "passive"))
      (node (ref "R21") (pin "1") (pinfunction "1_1") (pintype "passive"))
      (node (ref "R22") (pin "2") (pinfunction "2_2") (pintype "passive"))
      (node (ref "R23") (pin "1") (pinfunction "1_1") (pintype "passive"))
      (node (ref "R24") (pin "1") (pinfunction "1_1") (pintype "passive"))
      (node (ref "R26") (pin "2") (pinfunction "2_2") (pintype "passive"))
      (node (ref "R28") (pin "2") (pinfunction "2_2") (pintype "passive"))
      (node (ref "T1") (pin "E") (pinfunction "E_E") (pintype "passive"))
      (node (ref "U$17") (pin "3") (pinfunction "0_3") (pintype "passive"))
      (node (ref "U$22") (pin "10") (pinfunction "GND_10") (pintype "bidirectional"))
      (node (ref "U$22") (pin "21") (pinfunction "GND_21") (pintype "bidirectional"))
      (node (ref "U$22") (pin "22") (pinfunction "GND_22") (pintype "bidirectional"))
      (node (ref "U$22") (pin "9") (pinfunction "GND_9") (pintype "bidirectional"))
      (node (ref "U$24") (pin "3") (pinfunction "0_3") (pintype "passive"))
      (node (ref "U$35") (pin "4") (pinfunction "GND_4") (pintype "bidirectional"))
      (node (ref "U$35") (pin "THER") (pinfunction "THER_THER") (pintype "bidirectional"))
      (node (ref "U$5") (pin "33") (pinfunction "EP/AVSS_33") (pintype "bidirectional"))
      (node (ref "U2") (pin "2") (pinfunction "VSS_2") (pintype "power_in"))
      (node (ref "U3") (pin "1") (pinfunction "SDO/SA0_1") (pintype "bidirectional"))
      (node (ref "U3") (pin "2") (pinfunction "SDX_2") (pintype "bidirectional"))
      (node (ref "U3") (pin "3") (pinfunction "SCX_3") (pintype "bidirectional"))
      (node (ref "U3") (pin "6") (pinfunction "GND_6") (pintype "bidirectional"))
      (node (ref "U3") (pin "7") (pinfunction "GND_7") (pintype "bidirectional"))
      (node (ref "U4") (pin "6") (pinfunction "GND_6") (pintype "passive"))
    )
    (net (code "11") (name "GP0") (class "Default")
      (node (ref "JMP2") (pin "1") (pinfunction "1_1") (pintype "passive"))
      (node (ref "U$5") (pin "7") (pinfunction "GPIO0_7") (pintype "bidirectional"))
    )
    (net (code "12") (name "GP1") (class "Default")
      (node (ref "MDBT1") (pin "32") (pinfunction "P0.02/NFC1_32") (pintype "bidirectional"))
      (node (ref "R27") (pin "2") (pinfunction "2_2") (pintype "passive"))
    )
    (net (code "13") (name "GP2") (class "Default")
      (node (ref "MDBT1") (pin "20") (pinfunction "P0.07/AIN3_20") (pintype "bidirectional"))
      (node (ref "R29") (pin "2") (pinfunction "2_2") (pintype "passive"))
    )
    (net (code "14") (name "Net-(C22-Pad1)") (class "Default")
      (node (ref "C22") (pin "1") (pinfunction "1_1") (pintype "passive"))
      (node (ref "R19") (pin "1") (pinfunction "1_1") (pintype "passive"))
      (node (ref "R7") (pin "1") (pinfunction "1_1") (pintype "passive"))
    )
    (net (code "15") (name "Net-(D7-A1)") (class "Default")
      (node (ref "D7") (pin "1") (pinfunction "A1_1") (pintype "passive"))
      (node (ref "R7") (pin "2") (pinfunction "2_2") (pintype "passive"))
    )
    (net (code "16") (name "Net-(D7-K1K2)") (class "Default")
      (node (ref "C9") (pin "1") (pinfunction "1_1") (pintype "passive"))
      (node (ref "D7") (pin "3") (pinfunction "K1K2_3") (pintype "passive"))
      (node (ref "R19") (pin "2") (pinfunction "2_2") (pintype "passive"))
      (node (ref "U2") (pin "5") (pinfunction "VDD_5") (pintype "power_in"))
    )
    (net (code "17") (name "Net-(J2-DN1)") (class "Default")
      (node (ref "D4") (pin "2") (pinfunction "2_2") (pintype "bidirectional"))
      (node (ref "J2") (pin "A7") (pinfunction "DN1_A7") (pintype "bidirectional"))
      (node (ref "J2") (pin "B7") (pinfunction "DN2_B7") (pintype "bidirectional"))
      (node (ref "R32") (pin "1") (pinfunction "1_1") (pintype "passive"))
    )
    (net (code "18") (name "Net-(J2-DP1)") (class "Default")
      (node (ref "D3") (pin "2") (pinfunction "2_2") (pintype "bidirectional"))
      (node (ref "J2") (pin "A6") (pinfunction "DP1_A6") (pintype "bidirectional"))
      (node (ref "J2") (pin "B6") (pinfunction "DP2_B6") (pintype "bidirectional"))
      (node (ref "R31") (pin "1") (pinfunction "1_1") (pintype "passive"))
    )
    (net (code "19") (name "Net-(J2-SBU1)") (class "Default")
      (node (ref "J2") (pin "A8") (pinfunction "SBU1_A8") (pintype "bidirectional"))
      (node (ref "R4") (pin "1") (pinfunction "1_1") (pintype "passive"))
    )
    (net (code "20") (name "Net-(J2-SBU2)") (class "Default")
      (node (ref "J2") (pin "B8") (pinfunction "SBU2_B8") (pintype "bidirectional"))
      (node (ref "R2") (pin "1") (pinfunction "1_1") (pintype "passive"))
    )
    (net (code "21") (name "Net-(JMP2-Pad2)") (class "Default")
      (node (ref "JMP2") (pin "2") (pinfunction "2_2") (pintype "passive"))
      (node (ref "R10") (pin "2") (pinfunction "2_2") (pintype "passive"))
      (node (ref "U$24") (pin "2") (pinfunction "1_2") (pintype "passive"))
    )
    (net (code "22") (name "Net-(JMP3-Pad2)") (class "Default")
      (node (ref "JMP3") (pin "2") (pinfunction "2_2") (pintype "passive"))
      (node (ref "R8") (pin "2") (pinfunction "2_2") (pintype "passive"))
      (node (ref "U$17") (pin "2") (pinfunction "1_2") (pintype "passive"))
    )
    (net (code "23") (name "Net-(MDBT1-DCC)") (class "Default")
      (node (ref "L2") (pin "1") (pinfunction "1_1") (pintype "passive"))
      (node (ref "MDBT1") (pin "54") (pinfunction "DCC_54") (pintype "bidirectional"))
    )
    (net (code "24") (name "Net-(MDBT1-DCCD)") (class "Default")
      (node (ref "L1") (pin "1") (pinfunction "1_1") (pintype "passive"))
      (node (ref "MDBT1") (pin "50") (pinfunction "DCCD_50") (pintype "bidirectional"))
    )
    (net (code "25") (name "Net-(MDBT1-DCCH)") (class "Default")
      (node (ref "L3") (pin "2") (pinfunction "2_2") (pintype "passive"))
      (node (ref "MDBT1") (pin "40") (pinfunction "DCCH_40") (pintype "bidirectional"))
    )
    (net (code "26") (name "Net-(MDBT1-DECD)") (class "Default")
      (node (ref "C14") (pin "1") (pinfunction "1_1") (pintype "passive"))
      (node (ref "L1") (pin "2") (pinfunction "2_2") (pintype "passive"))
      (node (ref "MDBT1") (pin "52") (pinfunction "DECD_52") (pintype "bidirectional"))
    )
    (net (code "27") (name "Net-(MDBT1-DECR)") (class "Default")
      (node (ref "C13") (pin "1") (pinfunction "1_1") (pintype "passive"))
      (node (ref "L2") (pin "2") (pinfunction "2_2") (pintype "passive"))
      (node (ref "MDBT1") (pin "58") (pinfunction "DECR_58") (pintype "bidirectional"))
    )
    (net (code "28") (name "Net-(MDBT1-P0.00{slash}XL1)") (class "Default")
      (node (ref "C15") (pin "2") (pinfunction "2_2") (pintype "passive"))
      (node (ref "MDBT1") (pin "34") (pinfunction "P0.00/XL1_34") (pintype "bidirectional"))
      (node (ref "U$19") (pin "P$2") (pinfunction "2_P$2") (pintype "passive"))
    )
    (net (code "29") (name "Net-(MDBT1-P0.01{slash}XL2)") (class "Default")
      (node (ref "C12") (pin "1") (pinfunction "1_1") (pintype "passive"))
      (node (ref "MDBT1") (pin "36") (pinfunction "P0.01/XL2_36") (pintype "bidirectional"))
      (node (ref "U$19") (pin "P$1") (pinfunction "1_P$1") (pintype "passive"))
    )
    (net (code "30") (name "Net-(MDBT1-P0.19)") (class "Default")
      (node (ref "MDBT1") (pin "14") (pinfunction "P0.19_14") (pintype "bidirectional"))
      (node (ref "P19") (pin "TP") (pinfunction "TP_TP") (pintype "input"))
    )
    (net (code "31") (name "Net-(MDBT1-P0.21)") (class "Default")
      (node (ref "MDBT1") (pin "12") (pinfunction "P0.21_12") (pintype "bidirectional"))
      (node (ref "P21") (pin "TP") (pinfunction "TP_TP") (pintype "input"))
    )
    (net (code "32") (name "Net-(MDBT1-VDDH)") (class "Default")
      (node (ref "MDBT1") (pin "41") (pinfunction "VDDH_41") (pintype "bidirectional"))
      (node (ref "R34") (pin "2") (pinfunction "2_2") (pintype "passive"))
    )
    (net (code "33") (name "Net-(Q2-S)") (class "Default")
      (node (ref "D8") (pin "A") (pinfunction "A_A") (pintype "passive"))
      (node (ref "Q2") (pin "2") (pinfunction "S_2") (pintype "passive"))
    )
    (net (code "34") (name "Net-(R1-Pad1)") (class "Default")
      (node (ref "R1") (pin "1") (pinfunction "1_1") (pintype "passive"))
      (node (ref "R3") (pin "2") (pinfunction "2_2") (pintype "passive"))
      (node (ref "T1") (pin "B") (pinfunction "B_B") (pintype "passive"))
    )
    (net (code "35") (name "Net-(R5-Pad1)") (class "Default")
      (node (ref "R5") (pin "1") (pinfunction "1_1") (pintype "passive"))
      (node (ref "T1") (pin "C") (pinfunction "C_C") (pintype "passive"))
    )
    (net (code "36") (name "Net-(U$5-GPIO1)") (class "Default")
      (node (ref "R27") (pin "1") (pinfunction "1_1") (pintype "passive"))
      (node (ref "U$5") (pin "8") (pinfunction "GPIO1_8") (pintype "bidirectional"))
    )
    (net (code "37") (name "Net-(U$5-GPIO2)") (class "Default")
      (node (ref "R29") (pin "1") (pinfunction "1_1") (pintype "passive"))
      (node (ref "U$5") (pin "9") (pinfunction "GPIO2_9") (pintype "bidirectional"))
    )
    (net (code "38") (name "Net-(U$5-NTC)") (class "Default")
      (node (ref "R22") (pin "1") (pinfunction "1_1") (pintype "passive"))
      (node (ref "U$5") (pin "18") (pinfunction "NTC_18") (pintype "bidirectional"))
    )
    (net (code "39") (name "Net-(U$5-PVSS1)") (class "Default")
      (node (ref "C1") (pin "2") (pinfunction "2_2") (pintype "passive"))
      (node (ref "C8") (pin "2") (pinfunction "2_2") (pintype "passive"))
      (node (ref "R24") (pin "2") (pinfunction "2_2") (pintype "passive"))
      (node (ref "U$5") (pin "2") (pinfunction "PVSS1_2") (pintype "bidirectional"))
    )
    (net (code "40") (name "Net-(U$5-PVSS2)") (class "Default")
      (node (ref "C17") (pin "2") (pinfunction "2_2") (pintype "passive"))
      (node (ref "C3") (pin "2") (pinfunction "2_2") (pintype "passive"))
      (node (ref "R23") (pin "2") (pinfunction "2_2") (pintype "passive"))
      (node (ref "U$5") (pin "6") (pinfunction "PVSS2_6") (pintype "bidirectional"))
    )
    (net (code "41") (name "Net-(U$5-SHPHLD)") (class "Default")
      (node (ref "R25") (pin "1") (pinfunction "1_1") (pintype "passive"))
      (node (ref "U$5") (pin "15") (pinfunction "SHPHLD_15") (pintype "bidirectional"))
    )
    (net (code "42") (name "Net-(U$5-SW1)") (class "Default")
      (node (ref "U$2") (pin "1") (pinfunction "1_1") (pintype "passive"))
      (node (ref "U$5") (pin "3") (pinfunction "SW1_3") (pintype "bidirectional"))
    )
    (net (code "43") (name "Net-(U$5-SW2)") (class "Default")
      (node (ref "U$3") (pin "1") (pinfunction "1_1") (pintype "passive"))
      (node (ref "U$5") (pin "5") (pinfunction "SW2_5") (pintype "bidirectional"))
    )
    (net (code "44") (name "Net-(U$5-VBAT)") (class "Default")
      (node (ref "BAT+1") (pin "TP") (pinfunction "TP_TP") (pintype "input"))
      (node (ref "C19") (pin "1") (pinfunction "1_1") (pintype "passive"))
      (node (ref "U$5") (pin "19") (pinfunction "VBAT_19") (pintype "bidirectional"))
    )
    (net (code "45") (name "Net-(U$5-VSET1)") (class "Default")
      (node (ref "R17") (pin "2") (pinfunction "2_2") (pintype "passive"))
      (node (ref "U$5") (pin "17") (pinfunction "VSET1_17") (pintype "bidirectional"))
    )
    (net (code "46") (name "Net-(U$5-VSET2)") (class "Default")
      (node (ref "R21") (pin "2") (pinfunction "2_2") (pintype "passive"))
      (node (ref "U$5") (pin "16") (pinfunction "VSET2_16") (pintype "bidirectional"))
    )
    (net (code "47") (name "Net-(U$22-LEDK1)") (class "Default")
      (node (ref "R5") (pin "2") (pinfunction "2_2") (pintype "passive"))
      (node (ref "U$22") (pin "11") (pinfunction "LEDK2_11") (pintype "bidirectional"))
      (node (ref "U$22") (pin "12") (pinfunction "LEDK1_12") (pintype "bidirectional"))
    )
    (net (code "48") (name "Net-(U$35-VCC)") (class "Default")
      (node (ref "C24") (pin "1") (pinfunction "1_1") (pintype "passive"))
      (node (ref "C25") (pin "1") (pinfunction "1_1") (pintype "passive"))
      (node (ref "C7") (pin "1") (pinfunction "1_1") (pintype "passive"))
      (node (ref "JMP4") (pin "2") (pinfunction "2_2") (pintype "passive"))
      (node (ref "U$35") (pin "8") (pinfunction "VCC_8") (pintype "bidirectional"))
    )
    (net (code "49") (name "Net-(U2-CLKOE)") (class "Default")
      (node (ref "R18") (pin "1") (pinfunction "1_1") (pintype "passive"))
      (node (ref "R20") (pin "2") (pinfunction "2_2") (pintype "passive"))
      (node (ref "U2") (pin "3") (pinfunction "CLKOE_3") (pintype "input"))
    )
    (net (code "50") (name "Net-(U4-SEL)") (class "Default")
      (node (ref "R13") (pin "2") (pinfunction "2_2") (pintype "passive"))
      (node (ref "R6") (pin "2") (pinfunction "2_2") (pintype "passive"))
      (node (ref "U4") (pin "15") (pinfunction "SEL_15") (pintype "passive"))
    )
    (net (code "51") (name "Net-(U4-~{EN})") (class "Default")
      (node (ref "JMP1") (pin "2") (pinfunction "2_2") (pintype "passive"))
      (node (ref "U4") (pin "13") (pinfunction "~{EN}_13") (pintype "passive"))
    )
    (net (code "52") (name "PPG_POWER") (class "Default")
      (node (ref "J4") (pin "1") (pinfunction "1_1") (pintype "passive"))
      (node (ref "J4") (pin "3") (pinfunction "3_3") (pintype "passive"))
      (node (ref "Q2") (pin "3") (pinfunction "D_3") (pintype "passive"))
    )
    (net (code "53") (name "QSPI-0") (class "Default")
      (node (ref "MDBT1") (pin "21") (pinfunction "P0.13/QSPI0_21") (pintype "bidirectional"))
      (node (ref "U$35") (pin "5") (pinfunction "DI(IO0)_5") (pintype "bidirectional"))
    )
    (net (code "54") (name "QSPI-1") (class "Default")
      (node (ref "MDBT1") (pin "27") (pinfunction "P0.14/QSPI1_27") (pintype "bidirectional"))
      (node (ref "U$35") (pin "2") (pinfunction "DO(IO1)_2") (pintype "bidirectional"))
    )
    (net (code "55") (name "QSPI-2") (class "Default")
      (node (ref "MDBT1") (pin "23") (pinfunction "P0.15/QSPI2_23") (pintype "bidirectional"))
      (node (ref "U$35") (pin "3") (pinfunction "WP(IO2)_3") (pintype "bidirectional"))
    )
    (net (code "56") (name "QSPI-3") (class "Default")
      (node (ref "MDBT1") (pin "28") (pinfunction "P0.16/QSPI3_28") (pintype "bidirectional"))
      (node (ref "U$35") (pin "7") (pinfunction "/HOLD(IO3)_7") (pintype "bidirectional"))
    )
    (net (code "57") (name "QSPI-CLK") (class "Default")
      (node (ref "MDBT1") (pin "26") (pinfunction "P0.17/QSPI_SCK_26") (pintype "bidirectional"))
      (node (ref "U$35") (pin "6") (pinfunction "CLK_6") (pintype "bidirectional"))
    )
    (net (code "58") (name "QSPI-CS") (class "Default")
      (node (ref "MDBT1") (pin "16") (pinfunction "P0.18/QSPI_CSN_16") (pintype "bidirectional"))
      (node (ref "U$35") (pin "1") (pinfunction "/CS_1") (pintype "bidirectional"))
    )
    (net (code "59") (name "RESET1") (class "Default")
      (node (ref "MDBT1") (pin "6") (pinfunction "RESET_6") (pintype "bidirectional"))
      (node (ref "P1") (pin "TP") (pinfunction "TP_TP") (pintype "input"))
    )
    (net (code "60") (name "RTC_INT") (class "Default")
      (node (ref "MDBT1") (pin "35") (pinfunction "P0.06/AIN2_35") (pintype "bidirectional"))
      (node (ref "R12") (pin "1") (pinfunction "1_1") (pintype "passive"))
      (node (ref "U2") (pin "4") (pinfunction "~{INT}_4") (pintype "output"))
    )
    (net (code "61") (name "S4A") (class "Default")
      (node (ref "J4") (pin "10") (pinfunction "10_10") (pintype "passive"))
      (node (ref "U4") (pin "12") (pinfunction "S4A_12") (pintype "bidirectional"))
    )
    (net (code "62") (name "S4B") (class "Default")
      (node (ref "J4") (pin "12") (pinfunction "12_12") (pintype "passive"))
      (node (ref "U4") (pin "11") (pinfunction "S4B_11") (pintype "bidirectional"))
    )
    (net (code "63") (name "SBU") (class "Default")
      (node (ref "D8") (pin "C") (pinfunction "C_C") (pintype "passive"))
      (node (ref "R2") (pin "2") (pinfunction "2_2") (pintype "passive"))
      (node (ref "R4") (pin "2") (pinfunction "2_2") (pintype "passive"))
    )
    (net (code "64") (name "SDO") (class "Default")
      (node (ref "U$22") (pin "6") (pinfunction "SDO_6") (pintype "bidirectional"))
    )
    (net (code "65") (name "SENSOR_BRD_SUPPLY") (class "Default")
      (node (ref "C20") (pin "1") (pinfunction "1_1") (pintype "passive"))
      (node (ref "C21") (pin "1") (pinfunction "1_1") (pintype "passive"))
      (node (ref "J3") (pin "1") (pinfunction "1_1") (pintype "passive"))
      (node (ref "J3") (pin "3") (pinfunction "3_3") (pintype "passive"))
      (node (ref "J3") (pin "5") (pinfunction "5_5") (pintype "passive"))
      (node (ref "J4") (pin "5") (pinfunction "5_5") (pintype "passive"))
      (node (ref "J4") (pin "7") (pinfunction "7_7") (pintype "passive"))
      (node (ref "J4") (pin "9") (pinfunction "9_9") (pintype "passive"))
      (node (ref "U$5") (pin "29") (pinfunction "LSOUT1/VOUTLDO1_29") (pintype "bidirectional"))
    )
    (net (code "66") (name "SEN_MFIO") (class "Default")
      (node (ref "J3") (pin "16") (pinfunction "16_16") (pintype "passive"))
      (node (ref "MDBT1") (pin "63") (pinfunction "P1.07_63") (pintype "bidirectional"))
    )
    (net (code "67") (name "SEN_MISO") (class "Default")
      (node (ref "J3") (pin "15") (pinfunction "15_15") (pintype "passive"))
      (node (ref "MDBT1") (pin "18") (pinfunction "P0.10/HSPI_MISO_18") (pintype "bidirectional"))
    )
    (net (code "68") (name "SEN_MOSI") (class "Default")
      (node (ref "J3") (pin "8") (pinfunction "8_8") (pintype "passive"))
      (node (ref "MDBT1") (pin "19") (pinfunction "P0.09/HSPI_MOSI_19") (pintype "bidirectional"))
    )
    (net (code "69") (name "SEN_RST") (class "Default")
      (node (ref "J3") (pin "19") (pinfunction "19_19") (pintype "passive"))
      (node (ref "MDBT1") (pin "10") (pinfunction "P1.06_10") (pintype "bidirectional"))
    )
    (net (code "70") (name "SEN_SCK") (class "Default")
      (node (ref "J3") (pin "4") (pinfunction "4_4") (pintype "passive"))
      (node (ref "MDBT1") (pin "29") (pinfunction "P0.08/HSPI_SCK_29") (pintype "bidirectional"))
    )
    (net (code "71") (name "SEN_SCL") (class "Default")
      (node (ref "J3") (pin "18") (pinfunction "18_18") (pintype "passive"))
      (node (ref "MDBT1") (pin "9") (pinfunction "P0.25/AIN4_9") (pintype "bidirectional"))
      (node (ref "R33") (pin "2") (pinfunction "2_2") (pintype "passive"))
      (node (ref "U$5") (pin "14") (pinfunction "SCL_14") (pintype "bidirectional"))
      (node (ref "U2") (pin "7") (pinfunction "SCL_7") (pintype "input"))
      (node (ref "U3") (pin "13") (pinfunction "SCL_13") (pintype "bidirectional"))
    )
    (net (code "72") (name "SEN_SDA") (class "Default")
      (node (ref "J3") (pin "17") (pinfunction "17_17") (pintype "passive"))
      (node (ref "MDBT1") (pin "8") (pinfunction "P0.24_8") (pintype "bidirectional"))
      (node (ref "R30") (pin "2") (pinfunction "2_2") (pintype "passive"))
      (node (ref "U$5") (pin "13") (pinfunction "SDA_13") (pintype "bidirectional"))
      (node (ref "U2") (pin "8") (pinfunction "SDA_8") (pintype "bidirectional"))
      (node (ref "U3") (pin "14") (pinfunction "SDA_14") (pintype "bidirectional"))
    )
    (net (code "73") (name "SHPHLD") (class "Default")
      (node (ref "JMP3") (pin "3") (pinfunction "3_3") (pintype "passive"))
      (node (ref "R25") (pin "2") (pinfunction "2_2") (pintype "passive"))
    )
    (net (code "74") (name "SW1") (class "Default")
      (node (ref "JMP2") (pin "3") (pinfunction "3_3") (pintype "passive"))
      (node (ref "MDBT1") (pin "39") (pinfunction "P0.05/AIN1_39") (pintype "bidirectional"))
    )
    (net (code "75") (name "SW3") (class "Default")
      (node (ref "JMP3") (pin "1") (pinfunction "1_1") (pintype "passive"))
      (node (ref "MDBT1") (pin "30") (pinfunction "P0.03/NFC2_30") (pintype "bidirectional"))
    )
    (net (code "76") (name "SWCLK1") (class "Default")
      (node (ref "J1") (pin "3") (pinfunction "3_3") (pintype "passive"))
      (node (ref "MDBT1") (pin "2") (pinfunction "SWDCLK_2") (pintype "bidirectional"))
      (node (ref "U4") (pin "4") (pinfunction "S2B_4") (pintype "bidirectional"))
    )
    (net (code "77") (name "SWDIO1") (class "Default")
      (node (ref "J1") (pin "4") (pinfunction "4_4") (pintype "passive"))
      (node (ref "MDBT1") (pin "4") (pinfunction "SWDIO_4") (pintype "bidirectional"))
      (node (ref "U4") (pin "1") (pinfunction "S1B_1") (pintype "bidirectional"))
    )
    (net (code "78") (name "SW_D1") (class "Default")
      (node (ref "D11") (pin "2") (pinfunction "2_2") (pintype "bidirectional"))
      (node (ref "J2") (pin "A2") (pinfunction "SSTXP1_A2") (pintype "bidirectional"))
      (node (ref "J2") (pin "B2") (pinfunction "SSTXP2_B2") (pintype "bidirectional"))
      (node (ref "U4") (pin "2") (pinfunction "D1_2") (pintype "bidirectional"))
    )
    (net (code "79") (name "SW_D2") (class "Default")
      (node (ref "D1") (pin "2") (pinfunction "2_2") (pintype "bidirectional"))
      (node (ref "J2") (pin "A3") (pinfunction "SSTXN1_A3") (pintype "bidirectional"))
      (node (ref "J2") (pin "B3") (pinfunction "SSTXN2_B3") (pintype "bidirectional"))
      (node (ref "U4") (pin "5") (pinfunction "D2_5") (pintype "bidirectional"))
    )
    (net (code "80") (name "SW_D3") (class "Default")
      (node (ref "D6") (pin "2") (pinfunction "2_2") (pintype "bidirectional"))
      (node (ref "J2") (pin "A11") (pinfunction "SSRXP2_A11") (pintype "bidirectional"))
      (node (ref "J2") (pin "B11") (pinfunction "SSRXP1_B11") (pintype "bidirectional"))
      (node (ref "U4") (pin "7") (pinfunction "D3_7") (pintype "bidirectional"))
    )
    (net (code "81") (name "SW_D4") (class "Default")
      (node (ref "D5") (pin "2") (pinfunction "2_2") (pintype "bidirectional"))
      (node (ref "J2") (pin "A10") (pinfunction "SSRXN2_A10") (pintype "bidirectional"))
      (node (ref "J2") (pin "B10") (pinfunction "SSRXN1_B10") (pintype "bidirectional"))
      (node (ref "U4") (pin "10") (pinfunction "D4_10") (pintype "bidirectional"))
    )
    (net (code "82") (name "S_INT") (class "Default")
      (node (ref "J4") (pin "8") (pinfunction "8_8") (pintype "passive"))
      (node (ref "U4") (pin "9") (pinfunction "S3A_9") (pintype "bidirectional"))
    )
    (net (code "83") (name "S_SCL") (class "Default")
      (node (ref "J4") (pin "6") (pinfunction "6_6") (pintype "passive"))
      (node (ref "U4") (pin "3") (pinfunction "S2A_3") (pintype "bidirectional"))
    )
    (net (code "84") (name "S_SDA") (class "Default")
      (node (ref "J4") (pin "4") (pinfunction "4_4") (pintype "passive"))
      (node (ref "U4") (pin "16") (pinfunction "S1A_16") (pintype "bidirectional"))
    )
    (net (code "85") (name "TFT_BL") (class "Default")
      (node (ref "MDBT1") (pin "22") (pinfunction "P1.05_22") (pintype "bidirectional"))
      (node (ref "R1") (pin "2") (pinfunction "2_2") (pintype "passive"))
    )
    (net (code "86") (name "TFT_CS") (class "Default")
      (node (ref "MDBT1") (pin "11") (pinfunction "P1.04_11") (pintype "bidirectional"))
      (node (ref "U$22") (pin "4") (pinfunction "CSX_4") (pintype "bidirectional"))
    )
    (net (code "87") (name "TFT_DC") (class "Default")
      (node (ref "MDBT1") (pin "43") (pinfunction "P1.01_43") (pintype "bidirectional"))
      (node (ref "U$22") (pin "8") (pinfunction "WRX/RS_8") (pintype "bidirectional"))
    )
    (net (code "88") (name "TFT_MOSI") (class "Default")
      (node (ref "MDBT1") (pin "51") (pinfunction "P1.13_51") (pintype "bidirectional"))
      (node (ref "U$22") (pin "7") (pinfunction "SDA_7") (pintype "bidirectional"))
    )
    (net (code "89") (name "TFT_RST") (class "Default")
      (node (ref "MDBT1") (pin "65") (pinfunction "P0.29_65") (pintype "bidirectional"))
      (node (ref "U$22") (pin "3") (pinfunction "RESET_3") (pintype "bidirectional"))
    )
    (net (code "90") (name "TFT_SCK") (class "Default")
      (node (ref "MDBT1") (pin "47") (pinfunction "P1.15_47") (pintype "bidirectional"))
      (node (ref "U$22") (pin "5") (pinfunction "DCX/SCL_5") (pintype "bidirectional"))
    )
    (net (code "91") (name "TP_INT") (class "Default")
      (node (ref "MDBT1") (pin "7") (pinfunction "P0.26/AIN5_7") (pintype "bidirectional"))
      (node (ref "U$22") (pin "16") (pinfunction "TP_INT_16") (pintype "bidirectional"))
    )
    (net (code "92") (name "TP_RST") (class "Default")
      (node (ref "MDBT1") (pin "5") (pinfunction "P0.27/AIN6_5") (pintype "bidirectional"))
      (node (ref "U$22") (pin "19") (pinfunction "TP_RST_19") (pintype "bidirectional"))
    )
    (net (code "93") (name "TP_SCL") (class "Default")
      (node (ref "MDBT1") (pin "31") (pinfunction "P1.03/TWI_31") (pintype "bidirectional"))
      (node (ref "R9") (pin "2") (pinfunction "2_2") (pintype "passive"))
      (node (ref "U$22") (pin "17") (pinfunction "TP_SCL_17") (pintype "bidirectional"))
    )
    (net (code "94") (name "TP_SDA") (class "Default")
      (node (ref "MDBT1") (pin "33") (pinfunction "P1.02/TWI_33") (pintype "bidirectional"))
      (node (ref "R11") (pin "2") (pinfunction "2_2") (pintype "passive"))
      (node (ref "U$22") (pin "18") (pinfunction "TP_SDA_18") (pintype "bidirectional"))
    )
    (net (code "95") (name "UART_TX") (class "Default")
      (node (ref "J1") (pin "2") (pinfunction "2_2") (pintype "power_in"))
      (node (ref "MDBT1") (pin "13") (pinfunction "P0.20_13") (pintype "bidirectional"))
      (node (ref "TX") (pin "TP") (pinfunction "TP_TP") (pintype "input"))
      (node (ref "U4") (pin "8") (pinfunction "S3B_8") (pintype "bidirectional"))
    )
    (net (code "96") (name "USB_D+") (class "Default")
      (node (ref "MDBT1") (pin "46") (pinfunction "D+_46") (pintype "bidirectional"))
      (node (ref "R31") (pin "2") (pinfunction "2_2") (pintype "passive"))
    )
    (net (code "97") (name "USB_D-") (class "Default")
      (node (ref "MDBT1") (pin "48") (pinfunction "D-_48") (pintype "bidirectional"))
      (node (ref "R32") (pin "2") (pinfunction "2_2") (pintype "passive"))
    )
    (net (code "98") (name "VBUS") (class "Default")
      (node (ref "MDBT1") (pin "44") (pinfunction "VBUS_44") (pintype "bidirectional"))
      (node (ref "U$5") (pin "22") (pinfunction "VBUSOUT_22") (pintype "bidirectional"))
    )
    (net (code "99") (name "VCC") (class "Default")
      (node (ref "C1") (pin "1") (pinfunction "1_1") (pintype "passive"))
      (node (ref "C3") (pin "1") (pinfunction "1_1") (pintype "passive"))
      (node (ref "C6") (pin "1") (pinfunction "1_1") (pintype "passive"))
      (node (ref "U$5") (pin "20") (pinfunction "VSYS_20") (pintype "bidirectional"))
      (node (ref "U$5") (pin "4") (pinfunction "PVDD_4") (pintype "bidirectional"))
    )
    (net (code "100") (name "VUSB2") (class "Default")
      (node (ref "C18") (pin "1") (pinfunction "1_1") (pintype "passive"))
      (node (ref "C5") (pin "1") (pinfunction "1_1") (pintype "passive"))
      (node (ref "J2") (pin "A4") (pinfunction "VBUS_A_A4") (pintype "power_in"))
      (node (ref "J2") (pin "A9") (pinfunction "VBUS_A_A9") (pintype "power_in"))
      (node (ref "J2") (pin "B4") (pinfunction "VBUS_B_B4") (pintype "power_in"))
      (node (ref "J2") (pin "B9") (pinfunction "VBUS_B_B9") (pintype "power_in"))
      (node (ref "Q2") (pin "1") (pinfunction "G_1") (pintype "passive"))
      (node (ref "R15") (pin "2") (pinfunction "2_2") (pintype "passive"))
      (node (ref "R6") (pin "1") (pinfunction "1_1") (pintype "passive"))
      (node (ref "U$5") (pin "21") (pinfunction "VBUS_21") (pintype "bidirectional"))
    )
    (net (code "101") (name "W_MFIO") (class "Default")
      (node (ref "J3") (pin "12") (pinfunction "12_12") (pintype "passive"))
      (node (ref "MDBT1") (pin "60") (pinfunction "P0.28/AIN7_60") (pintype "bidirectional"))
    )
    (net (code "102") (name "unconnected-(J3-Pad6)") (class "Default")
      (node (ref "J3") (pin "6") (pinfunction "6_6") (pintype "passive"))
    )
    (net (code "103") (name "unconnected-(J3-Pad7)") (class "Default")
      (node (ref "J3") (pin "7") (pinfunction "7_7") (pintype "passive"))
    )
    (net (code "104") (name "unconnected-(J3-Pad10)") (class "Default")
      (node (ref "J3") (pin "10") (pinfunction "10_10") (pintype "passive"))
    )
    (net (code "105") (name "unconnected-(J3-Pad13)") (class "Default")
      (node (ref "J3") (pin "13") (pinfunction "13_13") (pintype "passive"))
    )
    (net (code "106") (name "unconnected-(J4-Pad11)") (class "Default")
      (node (ref "J4") (pin "11") (pinfunction "11_11") (pintype "passive"))
    )
    (net (code "107") (name "unconnected-(J4-Pad13)") (class "Default")
      (node (ref "J4") (pin "13") (pinfunction "13_13") (pintype "passive"))
    )
    (net (code "108") (name "unconnected-(J4-Pad14)") (class "Default")
      (node (ref "J4") (pin "14") (pinfunction "14_14") (pintype "passive"))
    )
    (net (code "109") (name "unconnected-(MDBT1-P0.04{slash}AIN0-Pad37)") (class "Default")
      (node (ref "MDBT1") (pin "37") (pinfunction "P0.04/AIN0_37") (pintype "bidirectional"))
    )
    (net (code "110") (name "unconnected-(MDBT1-P0.11{slash}HSPI_CSN-Pad17)") (class "Default")
      (node (ref "MDBT1") (pin "17") (pinfunction "P0.11/HSPI_CSN_17") (pintype "bidirectional"))
    )
    (net (code "111") (name "unconnected-(MDBT1-P0.12{slash}HSPI_DCX-Pad15)") (class "Default")
      (node (ref "MDBT1") (pin "15") (pinfunction "P0.12/HSPI_DCX_15") (pintype "bidirectional"))
    )
    (net (code "112") (name "unconnected-(MDBT1-P0.22-Pad25)") (class "Default")
      (node (ref "MDBT1") (pin "25") (pinfunction "P0.22_25") (pintype "bidirectional"))
    )
    (net (code "113") (name "unconnected-(MDBT1-P0.23-Pad62)") (class "Default")
      (node (ref "MDBT1") (pin "62") (pinfunction "P0.23_62") (pintype "bidirectional"))
    )
    (net (code "114") (name "unconnected-(MDBT1-P0.30-Pad57)") (class "Default")
      (node (ref "MDBT1") (pin "57") (pinfunction "P0.30_57") (pintype "bidirectional"))
    )
    (net (code "115") (name "unconnected-(MDBT1-P0.31-Pad56)") (class "Default")
      (node (ref "MDBT1") (pin "56") (pinfunction "P0.31_56") (pintype "bidirectional"))
    )
    (net (code "116") (name "unconnected-(MDBT1-P1.00-Pad45)") (class "Default")
      (node (ref "MDBT1") (pin "45") (pinfunction "P1.00_45") (pintype "bidirectional"))
    )
    (net (code "117") (name "unconnected-(MDBT1-P1.12-Pad53)") (class "Default")
      (node (ref "MDBT1") (pin "53") (pinfunction "P1.12_53") (pintype "bidirectional"))
    )
    (net (code "118") (name "unconnected-(MDBT1-P1.14-Pad49)") (class "Default")
      (node (ref "MDBT1") (pin "49") (pinfunction "P1.14_49") (pintype "bidirectional"))
    )
    (net (code "119") (name "unconnected-(U$5-GPIO3-Pad10)") (class "Default")
      (node (ref "U$5") (pin "10") (pinfunction "GPIO3_10") (pintype "bidirectional"))
    )
    (net (code "120") (name "unconnected-(U$5-GPIO4-Pad11)") (class "Default")
      (node (ref "U$5") (pin "11") (pinfunction "GPIO4_11") (pintype "bidirectional"))
    )
    (net (code "121") (name "unconnected-(U$5-LED0-Pad25)") (class "Default")
      (node (ref "U$5") (pin "25") (pinfunction "LED0_25") (pintype "bidirectional"))
    )
    (net (code "122") (name "unconnected-(U$5-LED1-Pad26)") (class "Default")
      (node (ref "U$5") (pin "26") (pinfunction "LED1_26") (pintype "bidirectional"))
    )
    (net (code "123") (name "unconnected-(U$5-LED2-Pad27)") (class "Default")
      (node (ref "U$5") (pin "27") (pinfunction "LED2_27") (pintype "bidirectional"))
    )
    (net (code "124") (name "unconnected-(U$5-LSIN2{slash}VINLDO2-Pad30)") (class "Default")
      (node (ref "U$5") (pin "30") (pinfunction "LSIN2/VINLDO2_30") (pintype "bidirectional"))
    )
    (net (code "125") (name "unconnected-(U$5-LSOUT2{slash}VOUTLDO2-Pad31)") (class "Default")
      (node (ref "U$5") (pin "31") (pinfunction "LSOUT2/VOUTLDO2_31") (pintype "bidirectional"))
    )
    (net (code "126") (name "unconnected-(U$17-0-Pad1)") (class "Default")
      (node (ref "U$17") (pin "1") (pinfunction "0_1") (pintype "passive"))
    )
    (net (code "127") (name "unconnected-(U$17-1-Pad4)") (class "Default")
      (node (ref "U$17") (pin "4") (pinfunction "1_4") (pintype "passive"))
    )
    (net (code "128") (name "unconnected-(U$22-NC-Pad15)") (class "Default")
      (node (ref "U$22") (pin "15") (pinfunction "NC_15") (pintype "bidirectional"))
    )
    (net (code "129") (name "unconnected-(U$24-0-Pad1)") (class "Default")
      (node (ref "U$24") (pin "1") (pinfunction "0_1") (pintype "passive"))
    )
    (net (code "130") (name "unconnected-(U$24-1-Pad4)") (class "Default")
      (node (ref "U$24") (pin "4") (pinfunction "1_4") (pintype "passive"))
    )
    (net (code "131") (name "unconnected-(U2-CLKOUT-Pad6)") (class "Default")
      (node (ref "U2") (pin "6") (pinfunction "CLKOUT_6") (pintype "output"))
    )
    (net (code "132") (name "unconnected-(U2-NC-Pad1)") (class "Default")
      (node (ref "U2") (pin "1") (pinfunction "NC_1") (pintype "no_connect"))
    )
    (net (code "133") (name "unconnected-(U3-INT2-Pad9)") (class "Default")
      (node (ref "U3") (pin "9") (pinfunction "INT2_9") (pintype "bidirectional"))
    )
    (net (code "134") (name "unconnected-(U3-NC-Pad11)") (class "Default")
      (node (ref "U3") (pin "11") (pinfunction "NC_11") (pintype "bidirectional"))
    )
    (net (code "135") (name "unconnected-(U3-OCS-Pad10)") (class "Default")
      (node (ref "U3") (pin "10") (pinfunction "OCS_10") (pintype "bidirectional"))
    )
  )
)
